# PGTN029_sequential_switch.net
KiCad netlist of a schematic drawn in EAGLE
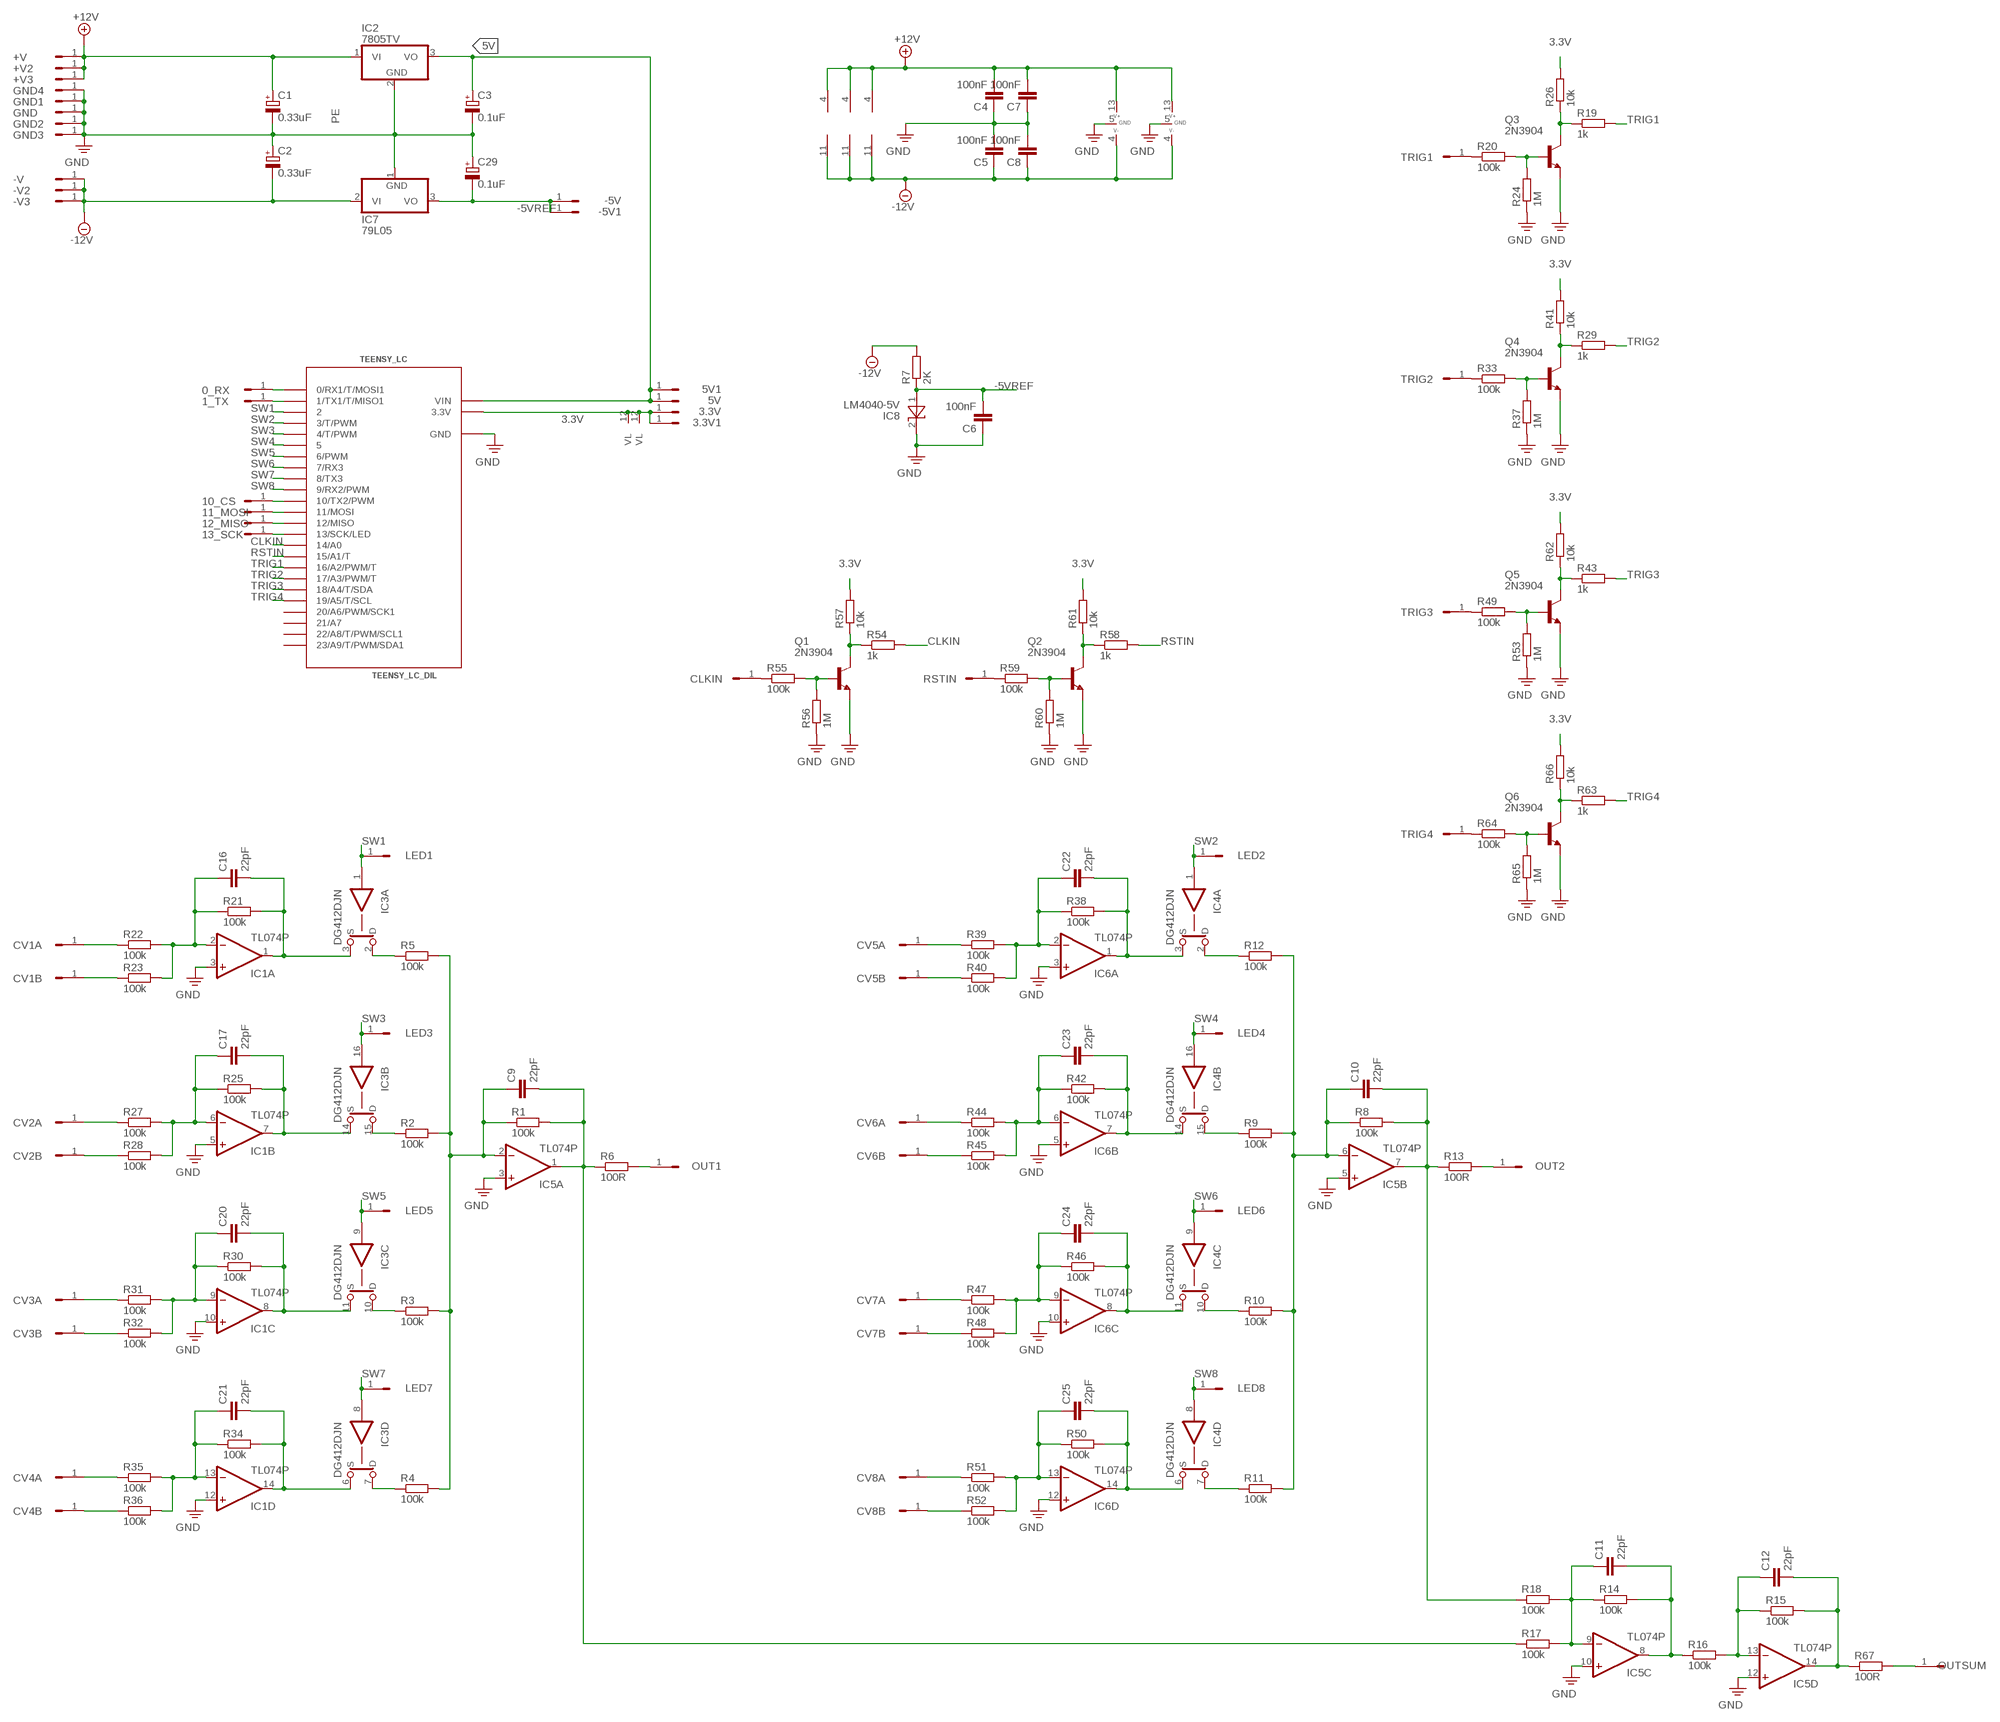
[diagram p0: schematic, sheet 1]

(export (version "E")
  (design (tool "Eeschema 10.0.6"))
  (components
    (comp (ref "+V")
      (value "HEADER/MALE/01")
      (footprint "eagle-import:HEADER_MALE_01")
      (fields (field (name "SPICEPREFIX") "X"))
      (libsource (lib "eagle-import") (part "HEADER/MALE/01"))
    )
    (comp (ref "+V2")
      (value "HEADER/MALE/01")
      (footprint "eagle-import:HEADER_MALE_01")
      (fields (field (name "SPICEPREFIX") "X"))
      (libsource (lib "eagle-import") (part "HEADER/MALE/01"))
    )
    (comp (ref "+V3")
      (value "HEADER/MALE/01")
      (footprint "eagle-import:HEADER_MALE_01")
      (fields (field (name "SPICEPREFIX") "X"))
      (libsource (lib "eagle-import") (part "HEADER/MALE/01"))
    )
    (comp (ref "-5V")
      (value "HEADER/MALE/01")
      (footprint "eagle-import:HEADER_MALE_01")
      (fields (field (name "SPICEPREFIX") "X"))
      (libsource (lib "eagle-import") (part "HEADER/MALE/01"))
    )
    (comp (ref "-5V1")
      (value "HEADER/MALE/01")
      (footprint "eagle-import:HEADER_MALE_01")
      (fields (field (name "SPICEPREFIX") "X"))
      (libsource (lib "eagle-import") (part "HEADER/MALE/01"))
    )
    (comp (ref "-V")
      (value "HEADER/MALE/01")
      (footprint "eagle-import:HEADER_MALE_01")
      (fields (field (name "SPICEPREFIX") "X"))
      (libsource (lib "eagle-import") (part "HEADER/MALE/01"))
    )
    (comp (ref "-V2")
      (value "HEADER/MALE/01")
      (footprint "eagle-import:HEADER_MALE_01")
      (fields (field (name "SPICEPREFIX") "X"))
      (libsource (lib "eagle-import") (part "HEADER/MALE/01"))
    )
    (comp (ref "-V3")
      (value "HEADER/MALE/01")
      (footprint "eagle-import:HEADER_MALE_01")
      (fields (field (name "SPICEPREFIX") "X"))
      (libsource (lib "eagle-import") (part "HEADER/MALE/01"))
    )
    (comp (ref "0_RX")
      (value "HEADER/MALE/01")
      (footprint "eagle-import:HEADER_MALE_01")
      (fields (field (name "SPICEPREFIX") "X"))
      (libsource (lib "eagle-import") (part "HEADER/MALE/01"))
    )
    (comp (ref "1_TX")
      (value "HEADER/MALE/01")
      (footprint "eagle-import:HEADER_MALE_01")
      (fields (field (name "SPICEPREFIX") "X"))
      (libsource (lib "eagle-import") (part "HEADER/MALE/01"))
    )
    (comp (ref "3.3V")
      (value "HEADER/MALE/01")
      (footprint "eagle-import:HEADER_MALE_01")
      (fields (field (name "SPICEPREFIX") "X"))
      (libsource (lib "eagle-import") (part "HEADER/MALE/01"))
    )
    (comp (ref "3.3V1")
      (value "HEADER/MALE/01")
      (footprint "eagle-import:HEADER_MALE_01")
      (fields (field (name "SPICEPREFIX") "X"))
      (libsource (lib "eagle-import") (part "HEADER/MALE/01"))
    )
    (comp (ref "5V")
      (value "HEADER/MALE/01")
      (footprint "eagle-import:HEADER_MALE_01")
      (fields (field (name "SPICEPREFIX") "X"))
      (libsource (lib "eagle-import") (part "HEADER/MALE/01"))
    )
    (comp (ref "5V1")
      (value "HEADER/MALE/01")
      (footprint "eagle-import:HEADER_MALE_01")
      (fields (field (name "SPICEPREFIX") "X"))
      (libsource (lib "eagle-import") (part "HEADER/MALE/01"))
    )
    (comp (ref "10_CS")
      (value "HEADER/MALE/01")
      (footprint "eagle-import:HEADER_MALE_01")
      (fields (field (name "SPICEPREFIX") "X"))
      (libsource (lib "eagle-import") (part "HEADER/MALE/01"))
    )
    (comp (ref "11_MOSI")
      (value "HEADER/MALE/01")
      (footprint "eagle-import:HEADER_MALE_01")
      (fields (field (name "SPICEPREFIX") "X"))
      (libsource (lib "eagle-import") (part "HEADER/MALE/01"))
    )
    (comp (ref "12_MISO")
      (value "HEADER/MALE/01")
      (footprint "eagle-import:HEADER_MALE_01")
      (fields (field (name "SPICEPREFIX") "X"))
      (libsource (lib "eagle-import") (part "HEADER/MALE/01"))
    )
    (comp (ref "13_SCK")
      (value "HEADER/MALE/01")
      (footprint "eagle-import:HEADER_MALE_01")
      (fields (field (name "SPICEPREFIX") "X"))
      (libsource (lib "eagle-import") (part "HEADER/MALE/01"))
    )
    (comp (ref "C1")
      (value "0.33uF")
      (footprint "eagle-import:E2,5-6")
      (fields (field (name "SPICEPREFIX") "C"))
      (libsource (lib "eagle-import") (part "CAPACITOR/POLARIZEDE2.5-6"))
    )
    (comp (ref "C2")
      (value "0.33uF")
      (footprint "eagle-import:E2,5-6")
      (fields (field (name "SPICEPREFIX") "C"))
      (libsource (lib "eagle-import") (part "CAPACITOR/POLARIZEDE2.5-6"))
    )
    (comp (ref "C3")
      (value "0.1uF")
      (footprint "eagle-import:E2,5-6")
      (fields (field (name "SPICEPREFIX") "C"))
      (libsource (lib "eagle-import") (part "CAPACITOR/POLARIZEDE2.5-6"))
    )
    (comp (ref "C4")
      (value "100nF")
      (footprint "eagle-import:CERAMICDISC_5")
      (libsource (lib "eagle-import") (part "CAPACITORCERAMICDISC/5"))
    )
    (comp (ref "C5")
      (value "100nF")
      (footprint "eagle-import:CERAMICDISC_5")
      (libsource (lib "eagle-import") (part "CAPACITORCERAMICDISC/5"))
    )
    (comp (ref "C6")
      (value "100nF")
      (footprint "eagle-import:CERAMICDISC_5")
      (libsource (lib "eagle-import") (part "CAPACITORCERAMICDISC/5"))
    )
    (comp (ref "C7")
      (value "100nF")
      (footprint "eagle-import:CERAMICDISC_5")
      (libsource (lib "eagle-import") (part "CAPACITORCERAMICDISC/5"))
    )
    (comp (ref "C8")
      (value "100nF")
      (footprint "eagle-import:CERAMICDISC_5")
      (libsource (lib "eagle-import") (part "CAPACITORCERAMICDISC/5"))
    )
    (comp (ref "C9")
      (value "22pF")
      (footprint "eagle-import:CERAMICDISC_5")
      (libsource (lib "eagle-import") (part "CAPACITORCERAMICDISC/5"))
    )
    (comp (ref "C10")
      (value "22pF")
      (footprint "eagle-import:CERAMICDISC_5")
      (libsource (lib "eagle-import") (part "CAPACITORCERAMICDISC/5"))
    )
    (comp (ref "C11")
      (value "22pF")
      (footprint "eagle-import:CERAMICDISC_5")
      (libsource (lib "eagle-import") (part "CAPACITORCERAMICDISC/5"))
    )
    (comp (ref "C12")
      (value "22pF")
      (footprint "eagle-import:CERAMICDISC_5")
      (libsource (lib "eagle-import") (part "CAPACITORCERAMICDISC/5"))
    )
    (comp (ref "C16")
      (value "22pF")
      (footprint "eagle-import:CERAMICDISC_5")
      (libsource (lib "eagle-import") (part "CAPACITORCERAMICDISC/5"))
    )
    (comp (ref "C17")
      (value "22pF")
      (footprint "eagle-import:CERAMICDISC_5")
      (libsource (lib "eagle-import") (part "CAPACITORCERAMICDISC/5"))
    )
    (comp (ref "C20")
      (value "22pF")
      (footprint "eagle-import:CERAMICDISC_5")
      (libsource (lib "eagle-import") (part "CAPACITORCERAMICDISC/5"))
    )
    (comp (ref "C21")
      (value "22pF")
      (footprint "eagle-import:CERAMICDISC_5")
      (libsource (lib "eagle-import") (part "CAPACITORCERAMICDISC/5"))
    )
    (comp (ref "C22")
      (value "22pF")
      (footprint "eagle-import:CERAMICDISC_5")
      (libsource (lib "eagle-import") (part "CAPACITORCERAMICDISC/5"))
    )
    (comp (ref "C23")
      (value "22pF")
      (footprint "eagle-import:CERAMICDISC_5")
      (libsource (lib "eagle-import") (part "CAPACITORCERAMICDISC/5"))
    )
    (comp (ref "C24")
      (value "22pF")
      (footprint "eagle-import:CERAMICDISC_5")
      (libsource (lib "eagle-import") (part "CAPACITORCERAMICDISC/5"))
    )
    (comp (ref "C25")
      (value "22pF")
      (footprint "eagle-import:CERAMICDISC_5")
      (libsource (lib "eagle-import") (part "CAPACITORCERAMICDISC/5"))
    )
    (comp (ref "C29")
      (value "0.1uF")
      (footprint "eagle-import:E2,5-6")
      (fields (field (name "SPICEPREFIX") "C"))
      (libsource (lib "eagle-import") (part "CAPACITOR/POLARIZEDE2.5-6"))
    )
    (comp (ref "CLKIN")
      (value "HEADER/MALE/01")
      (footprint "eagle-import:HEADER_MALE_01")
      (fields (field (name "SPICEPREFIX") "X"))
      (libsource (lib "eagle-import") (part "HEADER/MALE/01"))
    )
    (comp (ref "CV1A")
      (value "HEADER/MALE/01")
      (footprint "eagle-import:HEADER_MALE_01")
      (fields (field (name "SPICEPREFIX") "X"))
      (libsource (lib "eagle-import") (part "HEADER/MALE/01"))
    )
    (comp (ref "CV1B")
      (value "HEADER/MALE/01")
      (footprint "eagle-import:HEADER_MALE_01")
      (fields (field (name "SPICEPREFIX") "X"))
      (libsource (lib "eagle-import") (part "HEADER/MALE/01"))
    )
    (comp (ref "CV2A")
      (value "HEADER/MALE/01")
      (footprint "eagle-import:HEADER_MALE_01")
      (fields (field (name "SPICEPREFIX") "X"))
      (libsource (lib "eagle-import") (part "HEADER/MALE/01"))
    )
    (comp (ref "CV2B")
      (value "HEADER/MALE/01")
      (footprint "eagle-import:HEADER_MALE_01")
      (fields (field (name "SPICEPREFIX") "X"))
      (libsource (lib "eagle-import") (part "HEADER/MALE/01"))
    )
    (comp (ref "CV3A")
      (value "HEADER/MALE/01")
      (footprint "eagle-import:HEADER_MALE_01")
      (fields (field (name "SPICEPREFIX") "X"))
      (libsource (lib "eagle-import") (part "HEADER/MALE/01"))
    )
    (comp (ref "CV3B")
      (value "HEADER/MALE/01")
      (footprint "eagle-import:HEADER_MALE_01")
      (fields (field (name "SPICEPREFIX") "X"))
      (libsource (lib "eagle-import") (part "HEADER/MALE/01"))
    )
    (comp (ref "CV4A")
      (value "HEADER/MALE/01")
      (footprint "eagle-import:HEADER_MALE_01")
      (fields (field (name "SPICEPREFIX") "X"))
      (libsource (lib "eagle-import") (part "HEADER/MALE/01"))
    )
    (comp (ref "CV4B")
      (value "HEADER/MALE/01")
      (footprint "eagle-import:HEADER_MALE_01")
      (fields (field (name "SPICEPREFIX") "X"))
      (libsource (lib "eagle-import") (part "HEADER/MALE/01"))
    )
    (comp (ref "CV5A")
      (value "HEADER/MALE/01")
      (footprint "eagle-import:HEADER_MALE_01")
      (fields (field (name "SPICEPREFIX") "X"))
      (libsource (lib "eagle-import") (part "HEADER/MALE/01"))
    )
    (comp (ref "CV5B")
      (value "HEADER/MALE/01")
      (footprint "eagle-import:HEADER_MALE_01")
      (fields (field (name "SPICEPREFIX") "X"))
      (libsource (lib "eagle-import") (part "HEADER/MALE/01"))
    )
    (comp (ref "CV6A")
      (value "HEADER/MALE/01")
      (footprint "eagle-import:HEADER_MALE_01")
      (fields (field (name "SPICEPREFIX") "X"))
      (libsource (lib "eagle-import") (part "HEADER/MALE/01"))
    )
    (comp (ref "CV6B")
      (value "HEADER/MALE/01")
      (footprint "eagle-import:HEADER_MALE_01")
      (fields (field (name "SPICEPREFIX") "X"))
      (libsource (lib "eagle-import") (part "HEADER/MALE/01"))
    )
    (comp (ref "CV7A")
      (value "HEADER/MALE/01")
      (footprint "eagle-import:HEADER_MALE_01")
      (fields (field (name "SPICEPREFIX") "X"))
      (libsource (lib "eagle-import") (part "HEADER/MALE/01"))
    )
    (comp (ref "CV7B")
      (value "HEADER/MALE/01")
      (footprint "eagle-import:HEADER_MALE_01")
      (fields (field (name "SPICEPREFIX") "X"))
      (libsource (lib "eagle-import") (part "HEADER/MALE/01"))
    )
    (comp (ref "CV8A")
      (value "HEADER/MALE/01")
      (footprint "eagle-import:HEADER_MALE_01")
      (fields (field (name "SPICEPREFIX") "X"))
      (libsource (lib "eagle-import") (part "HEADER/MALE/01"))
    )
    (comp (ref "CV8B")
      (value "HEADER/MALE/01")
      (footprint "eagle-import:HEADER_MALE_01")
      (fields (field (name "SPICEPREFIX") "X"))
      (libsource (lib "eagle-import") (part "HEADER/MALE/01"))
    )
    (comp (ref "GND")
      (value "HEADER/MALE/01")
      (footprint "eagle-import:HEADER_MALE_01")
      (fields (field (name "SPICEPREFIX") "X"))
      (libsource (lib "eagle-import") (part "HEADER/MALE/01"))
    )
    (comp (ref "GND1")
      (value "HEADER/MALE/01")
      (footprint "eagle-import:HEADER_MALE_01")
      (fields (field (name "SPICEPREFIX") "X"))
      (libsource (lib "eagle-import") (part "HEADER/MALE/01"))
    )
    (comp (ref "GND2")
      (value "HEADER/MALE/01")
      (footprint "eagle-import:HEADER_MALE_01")
      (fields (field (name "SPICEPREFIX") "X"))
      (libsource (lib "eagle-import") (part "HEADER/MALE/01"))
    )
    (comp (ref "GND3")
      (value "HEADER/MALE/01")
      (footprint "eagle-import:HEADER_MALE_01")
      (fields (field (name "SPICEPREFIX") "X"))
      (libsource (lib "eagle-import") (part "HEADER/MALE/01"))
    )
    (comp (ref "GND4")
      (value "HEADER/MALE/01")
      (footprint "eagle-import:HEADER_MALE_01")
      (fields (field (name "SPICEPREFIX") "X"))
      (libsource (lib "eagle-import") (part "HEADER/MALE/01"))
    )
    (comp (ref "IC1")
      (value "TL074P")
      (footprint "eagle-import:DIL14")
      (libsource (lib "eagle-import") (part "TL074P"))
    )
    (comp (ref "IC2")
      (value "7805TV")
      (footprint "eagle-import:TO220V")
      (libsource (lib "eagle-import") (part "78TV05"))
    )
    (comp (ref "IC3")
      (value "DG412DJN")
      (footprint "eagle-import:DIL16")
      (libsource (lib "eagle-import") (part "DG412DJN"))
    )
    (comp (ref "IC4")
      (value "DG412DJN")
      (footprint "eagle-import:DIL16")
      (libsource (lib "eagle-import") (part "DG412DJN"))
    )
    (comp (ref "IC5")
      (value "TL074P")
      (footprint "eagle-import:DIL14")
      (libsource (lib "eagle-import") (part "TL074P"))
    )
    (comp (ref "IC6")
      (value "TL074P")
      (footprint "eagle-import:DIL14")
      (libsource (lib "eagle-import") (part "TL074P"))
    )
    (comp (ref "IC7")
      (value "79L05")
      (footprint "eagle-import:TO92")
      (libsource (lib "eagle-import") (part "79ZL05"))
    )
    (comp (ref "IC8")
      (value "LM4040-5V")
      (footprint "eagle-import:TO92")
      (libsource (lib "eagle-import") (part "LM4040"))
    )
    (comp (ref "LED1")
      (value "HEADER/MALE/01")
      (footprint "eagle-import:HEADER_MALE_01")
      (fields (field (name "SPICEPREFIX") "X"))
      (libsource (lib "eagle-import") (part "HEADER/MALE/01"))
    )
    (comp (ref "LED2")
      (value "HEADER/MALE/01")
      (footprint "eagle-import:HEADER_MALE_01")
      (fields (field (name "SPICEPREFIX") "X"))
      (libsource (lib "eagle-import") (part "HEADER/MALE/01"))
    )
    (comp (ref "LED3")
      (value "HEADER/MALE/01")
      (footprint "eagle-import:HEADER_MALE_01")
      (fields (field (name "SPICEPREFIX") "X"))
      (libsource (lib "eagle-import") (part "HEADER/MALE/01"))
    )
    (comp (ref "LED4")
      (value "HEADER/MALE/01")
      (footprint "eagle-import:HEADER_MALE_01")
      (fields (field (name "SPICEPREFIX") "X"))
      (libsource (lib "eagle-import") (part "HEADER/MALE/01"))
    )
    (comp (ref "LED5")
      (value "HEADER/MALE/01")
      (footprint "eagle-import:HEADER_MALE_01")
      (fields (field (name "SPICEPREFIX") "X"))
      (libsource (lib "eagle-import") (part "HEADER/MALE/01"))
    )
    (comp (ref "LED6")
      (value "HEADER/MALE/01")
      (footprint "eagle-import:HEADER_MALE_01")
      (fields (field (name "SPICEPREFIX") "X"))
      (libsource (lib "eagle-import") (part "HEADER/MALE/01"))
    )
    (comp (ref "LED7")
      (value "HEADER/MALE/01")
      (footprint "eagle-import:HEADER_MALE_01")
      (fields (field (name "SPICEPREFIX") "X"))
      (libsource (lib "eagle-import") (part "HEADER/MALE/01"))
    )
    (comp (ref "LED8")
      (value "HEADER/MALE/01")
      (footprint "eagle-import:HEADER_MALE_01")
      (fields (field (name "SPICEPREFIX") "X"))
      (libsource (lib "eagle-import") (part "HEADER/MALE/01"))
    )
    (comp (ref "OUT1")
      (value "HEADER/MALE/01")
      (footprint "eagle-import:HEADER_MALE_01")
      (fields (field (name "SPICEPREFIX") "X"))
      (libsource (lib "eagle-import") (part "HEADER/MALE/01"))
    )
    (comp (ref "OUT2")
      (value "HEADER/MALE/01")
      (footprint "eagle-import:HEADER_MALE_01")
      (fields (field (name "SPICEPREFIX") "X"))
      (libsource (lib "eagle-import") (part "HEADER/MALE/01"))
    )
    (comp (ref "OUTSUM")
      (value "HEADER/MALE/01")
      (footprint "eagle-import:HEADER_MALE_01")
      (fields (field (name "SPICEPREFIX") "X"))
      (libsource (lib "eagle-import") (part "HEADER/MALE/01"))
    )
    (comp (ref "Q1")
      (value "2N3904")
      (footprint "eagle-import:TO92")
      (libsource (lib "eagle-import") (part "2N3904"))
    )
    (comp (ref "Q2")
      (value "2N3904")
      (footprint "eagle-import:TO92")
      (libsource (lib "eagle-import") (part "2N3904"))
    )
    (comp (ref "Q3")
      (value "2N3904")
      (footprint "eagle-import:TO92")
      (libsource (lib "eagle-import") (part "2N3904"))
    )
    (comp (ref "Q4")
      (value "2N3904")
      (footprint "eagle-import:TO92")
      (libsource (lib "eagle-import") (part "2N3904"))
    )
    (comp (ref "Q5")
      (value "2N3904")
      (footprint "eagle-import:TO92")
      (libsource (lib "eagle-import") (part "2N3904"))
    )
    (comp (ref "Q6")
      (value "2N3904")
      (footprint "eagle-import:TO92")
      (libsource (lib "eagle-import") (part "2N3904"))
    )
    (comp (ref "R1")
      (value "100k")
      (footprint "eagle-import:RESISTOR_7.5")
      (libsource (lib "eagle-import") (part "RESISTORRESISTOR/UPRIGHT/7.5"))
    )
    (comp (ref "R2")
      (value "100k")
      (footprint "eagle-import:RESISTOR_7.5")
      (libsource (lib "eagle-import") (part "RESISTORRESISTOR/UPRIGHT/7.5"))
    )
    (comp (ref "R3")
      (value "100k")
      (footprint "eagle-import:RESISTOR_7.5")
      (libsource (lib "eagle-import") (part "RESISTORRESISTOR/UPRIGHT/7.5"))
    )
    (comp (ref "R4")
      (value "100k")
      (footprint "eagle-import:RESISTOR_7.5")
      (libsource (lib "eagle-import") (part "RESISTORRESISTOR/UPRIGHT/7.5"))
    )
    (comp (ref "R5")
      (value "100k")
      (footprint "eagle-import:RESISTOR_7.5")
      (libsource (lib "eagle-import") (part "RESISTORRESISTOR/UPRIGHT/7.5"))
    )
    (comp (ref "R6")
      (value "100R")
      (footprint "eagle-import:RESISTOR_7.5")
      (libsource (lib "eagle-import") (part "RESISTORRESISTOR/UPRIGHT/7.5"))
    )
    (comp (ref "R7")
      (value "2K")
      (footprint "eagle-import:RESISTOR_7.5")
      (libsource (lib "eagle-import") (part "RESISTORRESISTOR/UPRIGHT/7.5"))
    )
    (comp (ref "R8")
      (value "100k")
      (footprint "eagle-import:RESISTOR_7.5")
      (libsource (lib "eagle-import") (part "RESISTORRESISTOR/UPRIGHT/7.5"))
    )
    (comp (ref "R9")
      (value "100k")
      (footprint "eagle-import:RESISTOR_7.5")
      (libsource (lib "eagle-import") (part "RESISTORRESISTOR/UPRIGHT/7.5"))
    )
    (comp (ref "R10")
      (value "100k")
      (footprint "eagle-import:RESISTOR_7.5")
      (libsource (lib "eagle-import") (part "RESISTORRESISTOR/UPRIGHT/7.5"))
    )
    (comp (ref "R11")
      (value "100k")
      (footprint "eagle-import:RESISTOR_7.5")
      (libsource (lib "eagle-import") (part "RESISTORRESISTOR/UPRIGHT/7.5"))
    )
    (comp (ref "R12")
      (value "100k")
      (footprint "eagle-import:RESISTOR_7.5")
      (libsource (lib "eagle-import") (part "RESISTORRESISTOR/UPRIGHT/7.5"))
    )
    (comp (ref "R13")
      (value "100R")
      (footprint "eagle-import:RESISTOR_7.5")
      (libsource (lib "eagle-import") (part "RESISTORRESISTOR/UPRIGHT/7.5"))
    )
    (comp (ref "R14")
      (value "100k")
      (footprint "eagle-import:RESISTOR_7.5")
      (libsource (lib "eagle-import") (part "RESISTORRESISTOR/UPRIGHT/7.5"))
    )
    (comp (ref "R15")
      (value "100k")
      (footprint "eagle-import:RESISTOR_7.5")
      (libsource (lib "eagle-import") (part "RESISTORRESISTOR/UPRIGHT/7.5"))
    )
    (comp (ref "R16")
      (value "100k")
      (footprint "eagle-import:RESISTOR_7.5")
      (libsource (lib "eagle-import") (part "RESISTORRESISTOR/UPRIGHT/7.5"))
    )
    (comp (ref "R17")
      (value "100k")
      (footprint "eagle-import:RESISTOR_7.5")
      (libsource (lib "eagle-import") (part "RESISTORRESISTOR/UPRIGHT/7.5"))
    )
    (comp (ref "R18")
      (value "100k")
      (footprint "eagle-import:RESISTOR_7.5")
      (libsource (lib "eagle-import") (part "RESISTORRESISTOR/UPRIGHT/7.5"))
    )
    (comp (ref "R19")
      (value "1k")
      (footprint "eagle-import:RESISTOR_7.5")
      (libsource (lib "eagle-import") (part "RESISTORRESISTOR/UPRIGHT/7.5"))
    )
    (comp (ref "R20")
      (value "100k")
      (footprint "eagle-import:RESISTOR_7.5")
      (libsource (lib "eagle-import") (part "RESISTORRESISTOR/UPRIGHT/7.5"))
    )
    (comp (ref "R21")
      (value "100k")
      (footprint "eagle-import:RESISTOR_7.5")
      (libsource (lib "eagle-import") (part "RESISTORRESISTOR/UPRIGHT/7.5"))
    )
    (comp (ref "R22")
      (value "100k")
      (footprint "eagle-import:RESISTOR_7.5")
      (libsource (lib "eagle-import") (part "RESISTORRESISTOR/UPRIGHT/7.5"))
    )
    (comp (ref "R23")
      (value "100k")
      (footprint "eagle-import:RESISTOR_7.5")
      (libsource (lib "eagle-import") (part "RESISTORRESISTOR/UPRIGHT/7.5"))
    )
    (comp (ref "R24")
      (value "1M")
      (footprint "eagle-import:RESISTOR_7.5")
      (libsource (lib "eagle-import") (part "RESISTORRESISTOR/UPRIGHT/7.5"))
    )
    (comp (ref "R25")
      (value "100k")
      (footprint "eagle-import:RESISTOR_7.5")
      (libsource (lib "eagle-import") (part "RESISTORRESISTOR/UPRIGHT/7.5"))
    )
    (comp (ref "R26")
      (value "10k")
      (footprint "eagle-import:RESISTOR_7.5")
      (libsource (lib "eagle-import") (part "RESISTORRESISTOR/UPRIGHT/7.5"))
    )
    (comp (ref "R27")
      (value "100k")
      (footprint "eagle-import:RESISTOR_7.5")
      (libsource (lib "eagle-import") (part "RESISTORRESISTOR/UPRIGHT/7.5"))
    )
    (comp (ref "R28")
      (value "100k")
      (footprint "eagle-import:RESISTOR_7.5")
      (libsource (lib "eagle-import") (part "RESISTORRESISTOR/UPRIGHT/7.5"))
    )
    (comp (ref "R29")
      (value "1k")
      (footprint "eagle-import:RESISTOR_7.5")
      (libsource (lib "eagle-import") (part "RESISTORRESISTOR/UPRIGHT/7.5"))
    )
    (comp (ref "R30")
      (value "100k")
      (footprint "eagle-import:RESISTOR_7.5")
      (libsource (lib "eagle-import") (part "RESISTORRESISTOR/UPRIGHT/7.5"))
    )
    (comp (ref "R31")
      (value "100k")
      (footprint "eagle-import:RESISTOR_7.5")
      (libsource (lib "eagle-import") (part "RESISTORRESISTOR/UPRIGHT/7.5"))
    )
    (comp (ref "R32")
      (value "100k")
      (footprint "eagle-import:RESISTOR_7.5")
      (libsource (lib "eagle-import") (part "RESISTORRESISTOR/UPRIGHT/7.5"))
    )
    (comp (ref "R33")
      (value "100k")
      (footprint "eagle-import:RESISTOR_7.5")
      (libsource (lib "eagle-import") (part "RESISTORRESISTOR/UPRIGHT/7.5"))
    )
    (comp (ref "R34")
      (value "100k")
      (footprint "eagle-import:RESISTOR_7.5")
      (libsource (lib "eagle-import") (part "RESISTORRESISTOR/UPRIGHT/7.5"))
    )
    (comp (ref "R35")
      (value "100k")
      (footprint "eagle-import:RESISTOR_7.5")
      (libsource (lib "eagle-import") (part "RESISTORRESISTOR/UPRIGHT/7.5"))
    )
    (comp (ref "R36")
      (value "100k")
      (footprint "eagle-import:RESISTOR_7.5")
      (libsource (lib "eagle-import") (part "RESISTORRESISTOR/UPRIGHT/7.5"))
    )
    (comp (ref "R37")
      (value "1M")
      (footprint "eagle-import:RESISTOR_7.5")
      (libsource (lib "eagle-import") (part "RESISTORRESISTOR/UPRIGHT/7.5"))
    )
    (comp (ref "R38")
      (value "100k")
      (footprint "eagle-import:RESISTOR_7.5")
      (libsource (lib "eagle-import") (part "RESISTORRESISTOR/UPRIGHT/7.5"))
    )
    (comp (ref "R39")
      (value "100k")
      (footprint "eagle-import:RESISTOR_7.5")
      (libsource (lib "eagle-import") (part "RESISTORRESISTOR/UPRIGHT/7.5"))
    )
    (comp (ref "R40")
      (value "100k")
      (footprint "eagle-import:RESISTOR_7.5")
      (libsource (lib "eagle-import") (part "RESISTORRESISTOR/UPRIGHT/7.5"))
    )
    (comp (ref "R41")
      (value "10k")
      (footprint "eagle-import:RESISTOR_7.5")
      (libsource (lib "eagle-import") (part "RESISTORRESISTOR/UPRIGHT/7.5"))
    )
    (comp (ref "R42")
      (value "100k")
      (footprint "eagle-import:RESISTOR_7.5")
      (libsource (lib "eagle-import") (part "RESISTORRESISTOR/UPRIGHT/7.5"))
    )
    (comp (ref "R43")
      (value "1k")
      (footprint "eagle-import:RESISTOR_7.5")
      (libsource (lib "eagle-import") (part "RESISTORRESISTOR/UPRIGHT/7.5"))
    )
    (comp (ref "R44")
      (value "100k")
      (footprint "eagle-import:RESISTOR_7.5")
      (libsource (lib "eagle-import") (part "RESISTORRESISTOR/UPRIGHT/7.5"))
    )
    (comp (ref "R45")
      (value "100k")
      (footprint "eagle-import:RESISTOR_7.5")
      (libsource (lib "eagle-import") (part "RESISTORRESISTOR/UPRIGHT/7.5"))
    )
    (comp (ref "R46")
      (value "100k")
      (footprint "eagle-import:RESISTOR_7.5")
      (libsource (lib "eagle-import") (part "RESISTORRESISTOR/UPRIGHT/7.5"))
    )
    (comp (ref "R47")
      (value "100k")
      (footprint "eagle-import:RESISTOR_7.5")
      (libsource (lib "eagle-import") (part "RESISTORRESISTOR/UPRIGHT/7.5"))
    )
    (comp (ref "R48")
      (value "100k")
      (footprint "eagle-import:RESISTOR_7.5")
      (libsource (lib "eagle-import") (part "RESISTORRESISTOR/UPRIGHT/7.5"))
    )
    (comp (ref "R49")
      (value "100k")
      (footprint "eagle-import:RESISTOR_7.5")
      (libsource (lib "eagle-import") (part "RESISTORRESISTOR/UPRIGHT/7.5"))
    )
    (comp (ref "R50")
      (value "100k")
      (footprint "eagle-import:RESISTOR_7.5")
      (libsource (lib "eagle-import") (part "RESISTORRESISTOR/UPRIGHT/7.5"))
    )
    (comp (ref "R51")
      (value "100k")
      (footprint "eagle-import:RESISTOR_7.5")
      (libsource (lib "eagle-import") (part "RESISTORRESISTOR/UPRIGHT/7.5"))
    )
    (comp (ref "R52")
      (value "100k")
      (footprint "eagle-import:RESISTOR_7.5")
      (libsource (lib "eagle-import") (part "RESISTORRESISTOR/UPRIGHT/7.5"))
    )
    (comp (ref "R53")
      (value "1M")
      (footprint "eagle-import:RESISTOR_7.5")
      (libsource (lib "eagle-import") (part "RESISTORRESISTOR/UPRIGHT/7.5"))
    )
    (comp (ref "R54")
      (value "1k")
      (footprint "eagle-import:RESISTOR_7.5")
      (libsource (lib "eagle-import") (part "RESISTORRESISTOR/UPRIGHT/7.5"))
    )
    (comp (ref "R55")
      (value "100k")
      (footprint "eagle-import:RESISTOR_7.5")
      (libsource (lib "eagle-import") (part "RESISTORRESISTOR/UPRIGHT/7.5"))
    )
    (comp (ref "R56")
      (value "1M")
      (footprint "eagle-import:RESISTOR_7.5")
      (libsource (lib "eagle-import") (part "RESISTORRESISTOR/UPRIGHT/7.5"))
    )
    (comp (ref "R57")
      (value "10k")
      (footprint "eagle-import:RESISTOR_7.5")
      (libsource (lib "eagle-import") (part "RESISTORRESISTOR/UPRIGHT/7.5"))
    )
    (comp (ref "R58")
      (value "1k")
      (footprint "eagle-import:RESISTOR_7.5")
      (libsource (lib "eagle-import") (part "RESISTORRESISTOR/UPRIGHT/7.5"))
    )
    (comp (ref "R59")
      (value "100k")
      (footprint "eagle-import:RESISTOR_7.5")
      (libsource (lib "eagle-import") (part "RESISTORRESISTOR/UPRIGHT/7.5"))
    )
    (comp (ref "R60")
      (value "1M")
      (footprint "eagle-import:RESISTOR_7.5")
      (libsource (lib "eagle-import") (part "RESISTORRESISTOR/UPRIGHT/7.5"))
    )
    (comp (ref "R61")
      (value "10k")
      (footprint "eagle-import:RESISTOR_7.5")
      (libsource (lib "eagle-import") (part "RESISTORRESISTOR/UPRIGHT/7.5"))
    )
    (comp (ref "R62")
      (value "10k")
      (footprint "eagle-import:RESISTOR_7.5")
      (libsource (lib "eagle-import") (part "RESISTORRESISTOR/UPRIGHT/7.5"))
    )
    (comp (ref "R63")
      (value "1k")
      (footprint "eagle-import:RESISTOR_7.5")
      (libsource (lib "eagle-import") (part "RESISTORRESISTOR/UPRIGHT/7.5"))
    )
    (comp (ref "R64")
      (value "100k")
      (footprint "eagle-import:RESISTOR_7.5")
      (libsource (lib "eagle-import") (part "RESISTORRESISTOR/UPRIGHT/7.5"))
    )
    (comp (ref "R65")
      (value "1M")
      (footprint "eagle-import:RESISTOR_7.5")
      (libsource (lib "eagle-import") (part "RESISTORRESISTOR/UPRIGHT/7.5"))
    )
    (comp (ref "R66")
      (value "10k")
      (footprint "eagle-import:RESISTOR_7.5")
      (libsource (lib "eagle-import") (part "RESISTORRESISTOR/UPRIGHT/7.5"))
    )
    (comp (ref "R67")
      (value "100R")
      (footprint "eagle-import:RESISTOR_7.5")
      (libsource (lib "eagle-import") (part "RESISTORRESISTOR/UPRIGHT/7.5"))
    )
    (comp (ref "RSTIN")
      (value "HEADER/MALE/01")
      (footprint "eagle-import:HEADER_MALE_01")
      (fields (field (name "SPICEPREFIX") "X"))
      (libsource (lib "eagle-import") (part "HEADER/MALE/01"))
    )
    (comp (ref "TEENSY_LC")
      (value "TEENSY_LC_DIL")
      (footprint "eagle-import:TEENSY_3.0-3.2&LC_DIL")
      (libsource (lib "eagle-import") (part "TEENSY_LC_DIL"))
    )
    (comp (ref "TRIG1")
      (value "HEADER/MALE/01")
      (footprint "eagle-import:HEADER_MALE_01")
      (fields (field (name "SPICEPREFIX") "X"))
      (libsource (lib "eagle-import") (part "HEADER/MALE/01"))
    )
    (comp (ref "TRIG2")
      (value "HEADER/MALE/01")
      (footprint "eagle-import:HEADER_MALE_01")
      (fields (field (name "SPICEPREFIX") "X"))
      (libsource (lib "eagle-import") (part "HEADER/MALE/01"))
    )
    (comp (ref "TRIG3")
      (value "HEADER/MALE/01")
      (footprint "eagle-import:HEADER_MALE_01")
      (fields (field (name "SPICEPREFIX") "X"))
      (libsource (lib "eagle-import") (part "HEADER/MALE/01"))
    )
    (comp (ref "TRIG4")
      (value "HEADER/MALE/01")
      (footprint "eagle-import:HEADER_MALE_01")
      (fields (field (name "SPICEPREFIX") "X"))
      (libsource (lib "eagle-import") (part "HEADER/MALE/01"))
    )
  )
  (nets
    (net (code "1") (name "+12V") (class "Default")
      (node (ref "+V") (pin "1") (pinfunction "3_1") (pintype "passive"))
      (node (ref "+V2") (pin "1") (pinfunction "3_1") (pintype "passive"))
      (node (ref "+V3") (pin "1") (pinfunction "3_1") (pintype "passive"))
      (node (ref "C1") (pin "+") (pinfunction "+_+") (pintype "passive"))
      (node (ref "C4") (pin "2") (pinfunction "2_2") (pintype "passive"))
      (node (ref "C7") (pin "2") (pinfunction "2_2") (pintype "passive"))
      (node (ref "IC1") (pin "4") (pinfunction "V+_4") (pintype "power_in"))
      (node (ref "IC2") (pin "1") (pinfunction "VI_1") (pintype "input"))
      (node (ref "IC3") (pin "13") (pinfunction "V+_13") (pintype "power_in"))
      (node (ref "IC4") (pin "13") (pinfunction "V+_13") (pintype "power_in"))
      (node (ref "IC5") (pin "4") (pinfunction "V+_4") (pintype "power_in"))
      (node (ref "IC6") (pin "4") (pinfunction "V+_4") (pintype "power_in"))
    )
    (net (code "2") (name "-12V") (class "Default")
      (node (ref "-V") (pin "1") (pinfunction "3_1") (pintype "passive"))
      (node (ref "-V2") (pin "1") (pinfunction "3_1") (pintype "passive"))
      (node (ref "-V3") (pin "1") (pinfunction "3_1") (pintype "passive"))
      (node (ref "C2") (pin "-") (pinfunction "-_-") (pintype "passive"))
      (node (ref "C5") (pin "1") (pinfunction "1_1") (pintype "passive"))
      (node (ref "C8") (pin "1") (pinfunction "1_1") (pintype "passive"))
      (node (ref "IC1") (pin "11") (pinfunction "V-_11") (pintype "power_in"))
      (node (ref "IC3") (pin "4") (pinfunction "V-_4") (pintype "power_in"))
      (node (ref "IC4") (pin "4") (pinfunction "V-_4") (pintype "power_in"))
      (node (ref "IC5") (pin "11") (pinfunction "V-_11") (pintype "power_in"))
      (node (ref "IC6") (pin "11") (pinfunction "V-_11") (pintype "power_in"))
      (node (ref "IC7") (pin "2") (pinfunction "VI_2") (pintype "input"))
      (node (ref "R7") (pin "2") (pinfunction "2_2") (pintype "passive"))
    )
    (net (code "3") (name "/-5VREF") (class "Default")
      (node (ref "-5V") (pin "1") (pinfunction "3_1") (pintype "passive"))
      (node (ref "-5V1") (pin "1") (pinfunction "3_1") (pintype "passive"))
      (node (ref "C29") (pin "-") (pinfunction "-_-") (pintype "passive"))
      (node (ref "C6") (pin "2") (pinfunction "2_2") (pintype "passive"))
      (node (ref "IC7") (pin "3") (pinfunction "VO_3") (pintype "passive"))
      (node (ref "IC8") (pin "1") (pinfunction "A_1") (pintype "output"))
      (node (ref "R7") (pin "1") (pinfunction "1_1") (pintype "passive"))
    )
    (net (code "4") (name "/3.3V") (class "Default")
      (node (ref "3.3V") (pin "1") (pinfunction "3_1") (pintype "passive"))
      (node (ref "3.3V1") (pin "1") (pinfunction "3_1") (pintype "passive"))
      (node (ref "IC3") (pin "12") (pinfunction "VL_12") (pintype "input"))
      (node (ref "IC4") (pin "12") (pinfunction "VL_12") (pintype "input"))
      (node (ref "R26") (pin "2") (pinfunction "2_2") (pintype "passive"))
      (node (ref "R41") (pin "2") (pinfunction "2_2") (pintype "passive"))
      (node (ref "R57") (pin "2") (pinfunction "2_2") (pintype "passive"))
      (node (ref "R61") (pin "2") (pinfunction "2_2") (pintype "passive"))
      (node (ref "R62") (pin "2") (pinfunction "2_2") (pintype "passive"))
      (node (ref "R66") (pin "2") (pinfunction "2_2") (pintype "passive"))
      (node (ref "TEENSY_LC") (pin "3.3V") (pinfunction "3.3V_3.3V") (pintype "power_in"))
    )
    (net (code "5") (name "/CLKIN") (class "Default")
      (node (ref "R54") (pin "2") (pinfunction "2_2") (pintype "passive"))
      (node (ref "TEENSY_LC") (pin "14/A0") (pinfunction "14/A0_14/A0") (pintype "bidirectional"))
    )
    (net (code "6") (name "/RSTIN") (class "Default")
      (node (ref "R58") (pin "2") (pinfunction "2_2") (pintype "passive"))
      (node (ref "TEENSY_LC") (pin "15/A1") (pinfunction "15/A1/T_15/A1") (pintype "bidirectional"))
    )
    (net (code "7") (name "/SW1") (class "Default")
      (node (ref "IC3") (pin "1") (pinfunction "IN_1") (pintype "input"))
      (node (ref "LED1") (pin "1") (pinfunction "3_1") (pintype "passive"))
      (node (ref "TEENSY_LC") (pin "2") (pinfunction "2_2") (pintype "bidirectional"))
    )
    (net (code "8") (name "/SW2") (class "Default")
      (node (ref "IC4") (pin "1") (pinfunction "IN_1") (pintype "input"))
      (node (ref "LED2") (pin "1") (pinfunction "3_1") (pintype "passive"))
      (node (ref "TEENSY_LC") (pin "3") (pinfunction "3/T/PWM_3") (pintype "bidirectional"))
    )
    (net (code "9") (name "/SW3") (class "Default")
      (node (ref "IC3") (pin "16") (pinfunction "IN_16") (pintype "input"))
      (node (ref "LED3") (pin "1") (pinfunction "3_1") (pintype "passive"))
      (node (ref "TEENSY_LC") (pin "4") (pinfunction "4/T/PWM_4") (pintype "bidirectional"))
    )
    (net (code "10") (name "/SW4") (class "Default")
      (node (ref "IC4") (pin "16") (pinfunction "IN_16") (pintype "input"))
      (node (ref "LED4") (pin "1") (pinfunction "3_1") (pintype "passive"))
      (node (ref "TEENSY_LC") (pin "5") (pinfunction "5_5") (pintype "bidirectional"))
    )
    (net (code "11") (name "/SW5") (class "Default")
      (node (ref "IC3") (pin "9") (pinfunction "IN_9") (pintype "input"))
      (node (ref "LED5") (pin "1") (pinfunction "3_1") (pintype "passive"))
      (node (ref "TEENSY_LC") (pin "6") (pinfunction "6/PWM_6") (pintype "bidirectional"))
    )
    (net (code "12") (name "/SW6") (class "Default")
      (node (ref "IC4") (pin "9") (pinfunction "IN_9") (pintype "input"))
      (node (ref "LED6") (pin "1") (pinfunction "3_1") (pintype "passive"))
      (node (ref "TEENSY_LC") (pin "7") (pinfunction "7/RX3_7") (pintype "bidirectional"))
    )
    (net (code "13") (name "/SW7") (class "Default")
      (node (ref "IC3") (pin "8") (pinfunction "IN_8") (pintype "input"))
      (node (ref "LED7") (pin "1") (pinfunction "3_1") (pintype "passive"))
      (node (ref "TEENSY_LC") (pin "8") (pinfunction "8/TX3_8") (pintype "bidirectional"))
    )
    (net (code "14") (name "/SW8") (class "Default")
      (node (ref "IC4") (pin "8") (pinfunction "IN_8") (pintype "input"))
      (node (ref "LED8") (pin "1") (pinfunction "3_1") (pintype "passive"))
      (node (ref "TEENSY_LC") (pin "9") (pinfunction "9/RX2/PWM_9") (pintype "bidirectional"))
    )
    (net (code "15") (name "/TRIG1") (class "Default")
      (node (ref "R19") (pin "2") (pinfunction "2_2") (pintype "passive"))
      (node (ref "TEENSY_LC") (pin "16/A2") (pinfunction "16/A2/PWM/T_16/A2") (pintype "bidirectional"))
    )
    (net (code "16") (name "/TRIG2") (class "Default")
      (node (ref "R29") (pin "2") (pinfunction "2_2") (pintype "passive"))
      (node (ref "TEENSY_LC") (pin "17/A3") (pinfunction "17/A3/PWM/T_17/A3") (pintype "bidirectional"))
    )
    (net (code "17") (name "/TRIG3") (class "Default")
      (node (ref "R43") (pin "2") (pinfunction "2_2") (pintype "passive"))
      (node (ref "TEENSY_LC") (pin "18/A4") (pinfunction "18/A4/T/SDA_18/A4") (pintype "bidirectional"))
    )
    (net (code "18") (name "/TRIG4") (class "Default")
      (node (ref "R63") (pin "2") (pinfunction "2_2") (pintype "passive"))
      (node (ref "TEENSY_LC") (pin "19/A5") (pinfunction "19/A5/T/SCL_19/A5") (pintype "bidirectional"))
    )
    (net (code "19") (name "5V") (class "Default")
      (node (ref "5V") (pin "1") (pinfunction "3_1") (pintype "passive"))
      (node (ref "5V1") (pin "1") (pinfunction "3_1") (pintype "passive"))
      (node (ref "C3") (pin "+") (pinfunction "+_+") (pintype "passive"))
      (node (ref "IC2") (pin "3") (pinfunction "VO_3") (pintype "passive"))
      (node (ref "TEENSY_LC") (pin "VIN") (pinfunction "VIN_VIN") (pintype "power_in"))
    )
    (net (code "20") (name "GND") (class "Default")
      (node (ref "C1") (pin "-") (pinfunction "-_-") (pintype "passive"))
      (node (ref "C2") (pin "+") (pinfunction "+_+") (pintype "passive"))
      (node (ref "C29") (pin "+") (pinfunction "+_+") (pintype "passive"))
      (node (ref "C3") (pin "-") (pinfunction "-_-") (pintype "passive"))
      (node (ref "C4") (pin "1") (pinfunction "1_1") (pintype "passive"))
      (node (ref "C5") (pin "2") (pinfunction "2_2") (pintype "passive"))
      (node (ref "C6") (pin "1") (pinfunction "1_1") (pintype "passive"))
      (node (ref "C7") (pin "1") (pinfunction "1_1") (pintype "passive"))
      (node (ref "C8") (pin "2") (pinfunction "2_2") (pintype "passive"))
      (node (ref "GND") (pin "1") (pinfunction "3_1") (pintype "passive"))
      (node (ref "GND1") (pin "1") (pinfunction "3_1") (pintype "passive"))
      (node (ref "GND2") (pin "1") (pinfunction "3_1") (pintype "passive"))
      (node (ref "GND3") (pin "1") (pinfunction "3_1") (pintype "passive"))
      (node (ref "GND4") (pin "1") (pinfunction "3_1") (pintype "passive"))
      (node (ref "IC1") (pin "10") (pinfunction "+IN_10") (pintype "input"))
      (node (ref "IC1") (pin "12") (pinfunction "+IN_12") (pintype "input"))
      (node (ref "IC1") (pin "3") (pinfunction "+IN_3") (pintype "input"))
      (node (ref "IC1") (pin "5") (pinfunction "+IN_5") (pintype "input"))
      (node (ref "IC2") (pin "2") (pinfunction "GND_2") (pintype "passive"))
      (node (ref "IC3") (pin "5") (pinfunction "GND_5") (pintype "power_in"))
      (node (ref "IC4") (pin "5") (pinfunction "GND_5") (pintype "power_in"))
      (node (ref "IC5") (pin "10") (pinfunction "+IN_10") (pintype "input"))
      (node (ref "IC5") (pin "12") (pinfunction "+IN_12") (pintype "input"))
      (node (ref "IC5") (pin "3") (pinfunction "+IN_3") (pintype "input"))
      (node (ref "IC5") (pin "5") (pinfunction "+IN_5") (pintype "input"))
      (node (ref "IC6") (pin "10") (pinfunction "+IN_10") (pintype "input"))
      (node (ref "IC6") (pin "12") (pinfunction "+IN_12") (pintype "input"))
      (node (ref "IC6") (pin "3") (pinfunction "+IN_3") (pintype "input"))
      (node (ref "IC6") (pin "5") (pinfunction "+IN_5") (pintype "input"))
      (node (ref "IC7") (pin "1") (pinfunction "GND_1") (pintype "passive"))
      (node (ref "IC8") (pin "2") (pinfunction "C_2") (pintype "input"))
      (node (ref "Q1") (pin "3") (pinfunction "E_3") (pintype "passive"))
      (node (ref "Q2") (pin "3") (pinfunction "E_3") (pintype "passive"))
      (node (ref "Q3") (pin "3") (pinfunction "E_3") (pintype "passive"))
      (node (ref "Q4") (pin "3") (pinfunction "E_3") (pintype "passive"))
      (node (ref "Q5") (pin "3") (pinfunction "E_3") (pintype "passive"))
      (node (ref "Q6") (pin "3") (pinfunction "E_3") (pintype "passive"))
      (node (ref "R24") (pin "1") (pinfunction "1_1") (pintype "passive"))
      (node (ref "R37") (pin "1") (pinfunction "1_1") (pintype "passive"))
      (node (ref "R53") (pin "1") (pinfunction "1_1") (pintype "passive"))
      (node (ref "R56") (pin "1") (pinfunction "1_1") (pintype "passive"))
      (node (ref "R60") (pin "1") (pinfunction "1_1") (pintype "passive"))
      (node (ref "R65") (pin "1") (pinfunction "1_1") (pintype "passive"))
      (node (ref "TEENSY_LC") (pin "AGND") (pinfunction "GND_AGND") (pintype "power_in"))
      (node (ref "TEENSY_LC") (pin "GND") (pinfunction "GND_GND") (pintype "power_in"))
    )
    (net (code "21") (name "Net-(0_RX-3)") (class "Default")
      (node (ref "0_RX") (pin "1") (pinfunction "3_1") (pintype "passive"))
      (node (ref "TEENSY_LC") (pin "0") (pinfunction "0/RX1/T/MOSI1_0") (pintype "bidirectional"))
    )
    (net (code "22") (name "Net-(1_TX-3)") (class "Default")
      (node (ref "1_TX") (pin "1") (pinfunction "3_1") (pintype "passive"))
      (node (ref "TEENSY_LC") (pin "1") (pinfunction "1/TX1/T/MISO1_1") (pintype "bidirectional"))
    )
    (net (code "23") (name "Net-(10_CS-3)") (class "Default")
      (node (ref "10_CS") (pin "1") (pinfunction "3_1") (pintype "passive"))
      (node (ref "TEENSY_LC") (pin "10") (pinfunction "10/TX2/PWM_10") (pintype "bidirectional"))
    )
    (net (code "24") (name "Net-(11_MOSI-3)") (class "Default")
      (node (ref "11_MOSI") (pin "1") (pinfunction "3_1") (pintype "passive"))
      (node (ref "TEENSY_LC") (pin "11") (pinfunction "11/MOSI_11") (pintype "bidirectional"))
    )
    (net (code "25") (name "Net-(12_MISO-3)") (class "Default")
      (node (ref "12_MISO") (pin "1") (pinfunction "3_1") (pintype "passive"))
      (node (ref "TEENSY_LC") (pin "12") (pinfunction "12/MISO_12") (pintype "bidirectional"))
    )
    (net (code "26") (name "Net-(13_SCK-3)") (class "Default")
      (node (ref "13_SCK") (pin "1") (pinfunction "3_1") (pintype "passive"))
      (node (ref "TEENSY_LC") (pin "13") (pinfunction "13/SCK/LED_13") (pintype "bidirectional"))
    )
    (net (code "27") (name "Net-(CLKIN-3)") (class "Default")
      (node (ref "CLKIN") (pin "1") (pinfunction "3_1") (pintype "passive"))
      (node (ref "R55") (pin "1") (pinfunction "1_1") (pintype "passive"))
    )
    (net (code "28") (name "Net-(CV1A-3)") (class "Default")
      (node (ref "CV1A") (pin "1") (pinfunction "3_1") (pintype "passive"))
      (node (ref "R22") (pin "1") (pinfunction "1_1") (pintype "passive"))
    )
    (net (code "29") (name "Net-(CV1B-3)") (class "Default")
      (node (ref "CV1B") (pin "1") (pinfunction "3_1") (pintype "passive"))
      (node (ref "R23") (pin "1") (pinfunction "1_1") (pintype "passive"))
    )
    (net (code "30") (name "Net-(CV2A-3)") (class "Default")
      (node (ref "CV2A") (pin "1") (pinfunction "3_1") (pintype "passive"))
      (node (ref "R27") (pin "1") (pinfunction "1_1") (pintype "passive"))
    )
    (net (code "31") (name "Net-(CV2B-3)") (class "Default")
      (node (ref "CV2B") (pin "1") (pinfunction "3_1") (pintype "passive"))
      (node (ref "R28") (pin "1") (pinfunction "1_1") (pintype "passive"))
    )
    (net (code "32") (name "Net-(CV3A-3)") (class "Default")
      (node (ref "CV3A") (pin "1") (pinfunction "3_1") (pintype "passive"))
      (node (ref "R31") (pin "1") (pinfunction "1_1") (pintype "passive"))
    )
    (net (code "33") (name "Net-(CV3B-3)") (class "Default")
      (node (ref "CV3B") (pin "1") (pinfunction "3_1") (pintype "passive"))
      (node (ref "R32") (pin "1") (pinfunction "1_1") (pintype "passive"))
    )
    (net (code "34") (name "Net-(CV4A-3)") (class "Default")
      (node (ref "CV4A") (pin "1") (pinfunction "3_1") (pintype "passive"))
      (node (ref "R35") (pin "1") (pinfunction "1_1") (pintype "passive"))
    )
    (net (code "35") (name "Net-(CV4B-3)") (class "Default")
      (node (ref "CV4B") (pin "1") (pinfunction "3_1") (pintype "passive"))
      (node (ref "R36") (pin "1") (pinfunction "1_1") (pintype "passive"))
    )
    (net (code "36") (name "Net-(CV5A-3)") (class "Default")
      (node (ref "CV5A") (pin "1") (pinfunction "3_1") (pintype "passive"))
      (node (ref "R39") (pin "1") (pinfunction "1_1") (pintype "passive"))
    )
    (net (code "37") (name "Net-(CV5B-3)") (class "Default")
      (node (ref "CV5B") (pin "1") (pinfunction "3_1") (pintype "passive"))
      (node (ref "R40") (pin "1") (pinfunction "1_1") (pintype "passive"))
    )
    (net (code "38") (name "Net-(CV6A-3)") (class "Default")
      (node (ref "CV6A") (pin "1") (pinfunction "3_1") (pintype "passive"))
      (node (ref "R44") (pin "1") (pinfunction "1_1") (pintype "passive"))
    )
    (net (code "39") (name "Net-(CV6B-3)") (class "Default")
      (node (ref "CV6B") (pin "1") (pinfunction "3_1") (pintype "passive"))
      (node (ref "R45") (pin "1") (pinfunction "1_1") (pintype "passive"))
    )
    (net (code "40") (name "Net-(CV7A-3)") (class "Default")
      (node (ref "CV7A") (pin "1") (pinfunction "3_1") (pintype "passive"))
      (node (ref "R47") (pin "1") (pinfunction "1_1") (pintype "passive"))
    )
    (net (code "41") (name "Net-(CV7B-3)") (class "Default")
      (node (ref "CV7B") (pin "1") (pinfunction "3_1") (pintype "passive"))
      (node (ref "R48") (pin "1") (pinfunction "1_1") (pintype "passive"))
    )
    (net (code "42") (name "Net-(CV8A-3)") (class "Default")
      (node (ref "CV8A") (pin "1") (pinfunction "3_1") (pintype "passive"))
      (node (ref "R51") (pin "1") (pinfunction "1_1") (pintype "passive"))
    )
    (net (code "43") (name "Net-(CV8B-3)") (class "Default")
      (node (ref "CV8B") (pin "1") (pinfunction "3_1") (pintype "passive"))
      (node (ref "R52") (pin "1") (pinfunction "1_1") (pintype "passive"))
    )
    (net (code "44") (name "Net-(IC1A--IN)") (class "Default")
      (node (ref "C16") (pin "1") (pinfunction "1_1") (pintype "passive"))
      (node (ref "IC1") (pin "2") (pinfunction "-IN_2") (pintype "input"))
      (node (ref "R21") (pin "1") (pinfunction "1_1") (pintype "passive"))
      (node (ref "R22") (pin "2") (pinfunction "2_2") (pintype "passive"))
      (node (ref "R23") (pin "2") (pinfunction "2_2") (pintype "passive"))
    )
    (net (code "45") (name "Net-(IC1A-OUT)") (class "Default")
      (node (ref "C16") (pin "2") (pinfunction "2_2") (pintype "passive"))
      (node (ref "IC1") (pin "1") (pinfunction "OUT_1") (pintype "output"))
      (node (ref "IC3") (pin "3") (pinfunction "S_3") (pintype "bidirectional"))
      (node (ref "R21") (pin "2") (pinfunction "2_2") (pintype "passive"))
    )
    (net (code "46") (name "Net-(IC1B--IN)") (class "Default")
      (node (ref "C17") (pin "1") (pinfunction "1_1") (pintype "passive"))
      (node (ref "IC1") (pin "6") (pinfunction "-IN_6") (pintype "input"))
      (node (ref "R25") (pin "1") (pinfunction "1_1") (pintype "passive"))
      (node (ref "R27") (pin "2") (pinfunction "2_2") (pintype "passive"))
      (node (ref "R28") (pin "2") (pinfunction "2_2") (pintype "passive"))
    )
    (net (code "47") (name "Net-(IC1B-OUT)") (class "Default")
      (node (ref "C17") (pin "2") (pinfunction "2_2") (pintype "passive"))
      (node (ref "IC1") (pin "7") (pinfunction "OUT_7") (pintype "output"))
      (node (ref "IC3") (pin "14") (pinfunction "S_14") (pintype "bidirectional"))
      (node (ref "R25") (pin "2") (pinfunction "2_2") (pintype "passive"))
    )
    (net (code "48") (name "Net-(IC1C--IN)") (class "Default")
      (node (ref "C20") (pin "1") (pinfunction "1_1") (pintype "passive"))
      (node (ref "IC1") (pin "9") (pinfunction "-IN_9") (pintype "input"))
      (node (ref "R30") (pin "1") (pinfunction "1_1") (pintype "passive"))
      (node (ref "R31") (pin "2") (pinfunction "2_2") (pintype "passive"))
      (node (ref "R32") (pin "2") (pinfunction "2_2") (pintype "passive"))
    )
    (net (code "49") (name "Net-(IC1C-OUT)") (class "Default")
      (node (ref "C20") (pin "2") (pinfunction "2_2") (pintype "passive"))
      (node (ref "IC1") (pin "8") (pinfunction "OUT_8") (pintype "output"))
      (node (ref "IC3") (pin "11") (pinfunction "S_11") (pintype "bidirectional"))
      (node (ref "R30") (pin "2") (pinfunction "2_2") (pintype "passive"))
    )
    (net (code "50") (name "Net-(IC1D--IN)") (class "Default")
      (node (ref "C21") (pin "1") (pinfunction "1_1") (pintype "passive"))
      (node (ref "IC1") (pin "13") (pinfunction "-IN_13") (pintype "input"))
      (node (ref "R34") (pin "1") (pinfunction "1_1") (pintype "passive"))
      (node (ref "R35") (pin "2") (pinfunction "2_2") (pintype "passive"))
      (node (ref "R36") (pin "2") (pinfunction "2_2") (pintype "passive"))
    )
    (net (code "51") (name "Net-(IC1D-OUT)") (class "Default")
      (node (ref "C21") (pin "2") (pinfunction "2_2") (pintype "passive"))
      (node (ref "IC1") (pin "14") (pinfunction "OUT_14") (pintype "output"))
      (node (ref "IC3") (pin "6") (pinfunction "S_6") (pintype "bidirectional"))
      (node (ref "R34") (pin "2") (pinfunction "2_2") (pintype "passive"))
    )
    (net (code "52") (name "Net-(IC3A-D)") (class "Default")
      (node (ref "IC3") (pin "2") (pinfunction "D_2") (pintype "bidirectional"))
      (node (ref "R5") (pin "1") (pinfunction "1_1") (pintype "passive"))
    )
    (net (code "53") (name "Net-(IC3B-D)") (class "Default")
      (node (ref "IC3") (pin "15") (pinfunction "D_15") (pintype "bidirectional"))
      (node (ref "R2") (pin "1") (pinfunction "1_1") (pintype "passive"))
    )
    (net (code "54") (name "Net-(IC3C-D)") (class "Default")
      (node (ref "IC3") (pin "10") (pinfunction "D_10") (pintype "bidirectional"))
      (node (ref "R3") (pin "1") (pinfunction "1_1") (pintype "passive"))
    )
    (net (code "55") (name "Net-(IC3D-D)") (class "Default")
      (node (ref "IC3") (pin "7") (pinfunction "D_7") (pintype "bidirectional"))
      (node (ref "R4") (pin "1") (pinfunction "1_1") (pintype "passive"))
    )
    (net (code "56") (name "Net-(IC4A-D)") (class "Default")
      (node (ref "IC4") (pin "2") (pinfunction "D_2") (pintype "bidirectional"))
      (node (ref "R12") (pin "1") (pinfunction "1_1") (pintype "passive"))
    )
    (net (code "57") (name "Net-(IC4A-S)") (class "Default")
      (node (ref "C22") (pin "2") (pinfunction "2_2") (pintype "passive"))
      (node (ref "IC4") (pin "3") (pinfunction "S_3") (pintype "bidirectional"))
      (node (ref "IC6") (pin "1") (pinfunction "OUT_1") (pintype "output"))
      (node (ref "R38") (pin "2") (pinfunction "2_2") (pintype "passive"))
    )
    (net (code "58") (name "Net-(IC4B-D)") (class "Default")
      (node (ref "IC4") (pin "15") (pinfunction "D_15") (pintype "bidirectional"))
      (node (ref "R9") (pin "1") (pinfunction "1_1") (pintype "passive"))
    )
    (net (code "59") (name "Net-(IC4B-S)") (class "Default")
      (node (ref "C23") (pin "2") (pinfunction "2_2") (pintype "passive"))
      (node (ref "IC4") (pin "14") (pinfunction "S_14") (pintype "bidirectional"))
      (node (ref "IC6") (pin "7") (pinfunction "OUT_7") (pintype "output"))
      (node (ref "R42") (pin "2") (pinfunction "2_2") (pintype "passive"))
    )
    (net (code "60") (name "Net-(IC4C-D)") (class "Default")
      (node (ref "IC4") (pin "10") (pinfunction "D_10") (pintype "bidirectional"))
      (node (ref "R10") (pin "1") (pinfunction "1_1") (pintype "passive"))
    )
    (net (code "61") (name "Net-(IC4C-S)") (class "Default")
      (node (ref "C24") (pin "2") (pinfunction "2_2") (pintype "passive"))
      (node (ref "IC4") (pin "11") (pinfunction "S_11") (pintype "bidirectional"))
      (node (ref "IC6") (pin "8") (pinfunction "OUT_8") (pintype "output"))
      (node (ref "R46") (pin "2") (pinfunction "2_2") (pintype "passive"))
    )
    (net (code "62") (name "Net-(IC4D-D)") (class "Default")
      (node (ref "IC4") (pin "7") (pinfunction "D_7") (pintype "bidirectional"))
      (node (ref "R11") (pin "1") (pinfunction "1_1") (pintype "passive"))
    )
    (net (code "63") (name "Net-(IC4D-S)") (class "Default")
      (node (ref "C25") (pin "2") (pinfunction "2_2") (pintype "passive"))
      (node (ref "IC4") (pin "6") (pinfunction "S_6") (pintype "bidirectional"))
      (node (ref "IC6") (pin "14") (pinfunction "OUT_14") (pintype "output"))
      (node (ref "R50") (pin "2") (pinfunction "2_2") (pintype "passive"))
    )
    (net (code "64") (name "Net-(IC5A--IN)") (class "Default")
      (node (ref "C9") (pin "1") (pinfunction "1_1") (pintype "passive"))
      (node (ref "IC5") (pin "2") (pinfunction "-IN_2") (pintype "input"))
      (node (ref "R1") (pin "1") (pinfunction "1_1") (pintype "passive"))
      (node (ref "R2") (pin "2") (pinfunction "2_2") (pintype "passive"))
      (node (ref "R3") (pin "2") (pinfunction "2_2") (pintype "passive"))
      (node (ref "R4") (pin "2") (pinfunction "2_2") (pintype "passive"))
      (node (ref "R5") (pin "2") (pinfunction "2_2") (pintype "passive"))
    )
    (net (code "65") (name "Net-(IC5A-OUT)") (class "Default")
      (node (ref "C9") (pin "2") (pinfunction "2_2") (pintype "passive"))
      (node (ref "IC5") (pin "1") (pinfunction "OUT_1") (pintype "output"))
      (node (ref "R1") (pin "2") (pinfunction "2_2") (pintype "passive"))
      (node (ref "R17") (pin "1") (pinfunction "1_1") (pintype "passive"))
      (node (ref "R6") (pin "1") (pinfunction "1_1") (pintype "passive"))
    )
    (net (code "66") (name "Net-(IC5B--IN)") (class "Default")
      (node (ref "C10") (pin "1") (pinfunction "1_1") (pintype "passive"))
      (node (ref "IC5") (pin "6") (pinfunction "-IN_6") (pintype "input"))
      (node (ref "R10") (pin "2") (pinfunction "2_2") (pintype "passive"))
      (node (ref "R11") (pin "2") (pinfunction "2_2") (pintype "passive"))
      (node (ref "R12") (pin "2") (pinfunction "2_2") (pintype "passive"))
      (node (ref "R8") (pin "1") (pinfunction "1_1") (pintype "passive"))
      (node (ref "R9") (pin "2") (pinfunction "2_2") (pintype "passive"))
    )
    (net (code "67") (name "Net-(IC5B-OUT)") (class "Default")
      (node (ref "C10") (pin "2") (pinfunction "2_2") (pintype "passive"))
      (node (ref "IC5") (pin "7") (pinfunction "OUT_7") (pintype "output"))
      (node (ref "R13") (pin "1") (pinfunction "1_1") (pintype "passive"))
      (node (ref "R18") (pin "1") (pinfunction "1_1") (pintype "passive"))
      (node (ref "R8") (pin "2") (pinfunction "2_2") (pintype "passive"))
    )
    (net (code "68") (name "Net-(IC5C--IN)") (class "Default")
      (node (ref "C11") (pin "1") (pinfunction "1_1") (pintype "passive"))
      (node (ref "IC5") (pin "9") (pinfunction "-IN_9") (pintype "input"))
      (node (ref "R14") (pin "1") (pinfunction "1_1") (pintype "passive"))
      (node (ref "R17") (pin "2") (pinfunction "2_2") (pintype "passive"))
      (node (ref "R18") (pin "2") (pinfunction "2_2") (pintype "passive"))
    )
    (net (code "69") (name "Net-(IC5C-OUT)") (class "Default")
      (node (ref "C11") (pin "2") (pinfunction "2_2") (pintype "passive"))
      (node (ref "IC5") (pin "8") (pinfunction "OUT_8") (pintype "output"))
      (node (ref "R14") (pin "2") (pinfunction "2_2") (pintype "passive"))
      (node (ref "R16") (pin "1") (pinfunction "1_1") (pintype "passive"))
    )
    (net (code "70") (name "Net-(IC5D--IN)") (class "Default")
      (node (ref "C12") (pin "1") (pinfunction "1_1") (pintype "passive"))
      (node (ref "IC5") (pin "13") (pinfunction "-IN_13") (pintype "input"))
      (node (ref "R15") (pin "1") (pinfunction "1_1") (pintype "passive"))
      (node (ref "R16") (pin "2") (pinfunction "2_2") (pintype "passive"))
    )
    (net (code "71") (name "Net-(IC5D-OUT)") (class "Default")
      (node (ref "C12") (pin "2") (pinfunction "2_2") (pintype "passive"))
      (node (ref "IC5") (pin "14") (pinfunction "OUT_14") (pintype "output"))
      (node (ref "R15") (pin "2") (pinfunction "2_2") (pintype "passive"))
      (node (ref "R67") (pin "1") (pinfunction "1_1") (pintype "passive"))
    )
    (net (code "72") (name "Net-(IC6A--IN)") (class "Default")
      (node (ref "C22") (pin "1") (pinfunction "1_1") (pintype "passive"))
      (node (ref "IC6") (pin "2") (pinfunction "-IN_2") (pintype "input"))
      (node (ref "R38") (pin "1") (pinfunction "1_1") (pintype "passive"))
      (node (ref "R39") (pin "2") (pinfunction "2_2") (pintype "passive"))
      (node (ref "R40") (pin "2") (pinfunction "2_2") (pintype "passive"))
    )
    (net (code "73") (name "Net-(IC6B--IN)") (class "Default")
      (node (ref "C23") (pin "1") (pinfunction "1_1") (pintype "passive"))
      (node (ref "IC6") (pin "6") (pinfunction "-IN_6") (pintype "input"))
      (node (ref "R42") (pin "1") (pinfunction "1_1") (pintype "passive"))
      (node (ref "R44") (pin "2") (pinfunction "2_2") (pintype "passive"))
      (node (ref "R45") (pin "2") (pinfunction "2_2") (pintype "passive"))
    )
    (net (code "74") (name "Net-(IC6C--IN)") (class "Default")
      (node (ref "C24") (pin "1") (pinfunction "1_1") (pintype "passive"))
      (node (ref "IC6") (pin "9") (pinfunction "-IN_9") (pintype "input"))
      (node (ref "R46") (pin "1") (pinfunction "1_1") (pintype "passive"))
      (node (ref "R47") (pin "2") (pinfunction "2_2") (pintype "passive"))
      (node (ref "R48") (pin "2") (pinfunction "2_2") (pintype "passive"))
    )
    (net (code "75") (name "Net-(IC6D--IN)") (class "Default")
      (node (ref "C25") (pin "1") (pinfunction "1_1") (pintype "passive"))
      (node (ref "IC6") (pin "13") (pinfunction "-IN_13") (pintype "input"))
      (node (ref "R50") (pin "1") (pinfunction "1_1") (pintype "passive"))
      (node (ref "R51") (pin "2") (pinfunction "2_2") (pintype "passive"))
      (node (ref "R52") (pin "2") (pinfunction "2_2") (pintype "passive"))
    )
    (net (code "76") (name "Net-(OUT1-3)") (class "Default")
      (node (ref "OUT1") (pin "1") (pinfunction "3_1") (pintype "passive"))
      (node (ref "R6") (pin "2") (pinfunction "2_2") (pintype "passive"))
    )
    (net (code "77") (name "Net-(OUT2-3)") (class "Default")
      (node (ref "OUT2") (pin "1") (pinfunction "3_1") (pintype "passive"))
      (node (ref "R13") (pin "2") (pinfunction "2_2") (pintype "passive"))
    )
    (net (code "78") (name "Net-(OUTSUM-3)") (class "Default")
      (node (ref "OUTSUM") (pin "1") (pinfunction "3_1") (pintype "passive"))
      (node (ref "R67") (pin "2") (pinfunction "2_2") (pintype "passive"))
    )
    (net (code "79") (name "Net-(Q1-B)") (class "Default")
      (node (ref "Q1") (pin "2") (pinfunction "B_2") (pintype "passive"))
      (node (ref "R55") (pin "2") (pinfunction "2_2") (pintype "passive"))
      (node (ref "R56") (pin "2") (pinfunction "2_2") (pintype "passive"))
    )
    (net (code "80") (name "Net-(Q1-C)") (class "Default")
      (node (ref "Q1") (pin "1") (pinfunction "C_1") (pintype "passive"))
      (node (ref "R54") (pin "1") (pinfunction "1_1") (pintype "passive"))
      (node (ref "R57") (pin "1") (pinfunction "1_1") (pintype "passive"))
    )
    (net (code "81") (name "Net-(Q2-B)") (class "Default")
      (node (ref "Q2") (pin "2") (pinfunction "B_2") (pintype "passive"))
      (node (ref "R59") (pin "2") (pinfunction "2_2") (pintype "passive"))
      (node (ref "R60") (pin "2") (pinfunction "2_2") (pintype "passive"))
    )
    (net (code "82") (name "Net-(Q2-C)") (class "Default")
      (node (ref "Q2") (pin "1") (pinfunction "C_1") (pintype "passive"))
      (node (ref "R58") (pin "1") (pinfunction "1_1") (pintype "passive"))
      (node (ref "R61") (pin "1") (pinfunction "1_1") (pintype "passive"))
    )
    (net (code "83") (name "Net-(Q3-B)") (class "Default")
      (node (ref "Q3") (pin "2") (pinfunction "B_2") (pintype "passive"))
      (node (ref "R20") (pin "2") (pinfunction "2_2") (pintype "passive"))
      (node (ref "R24") (pin "2") (pinfunction "2_2") (pintype "passive"))
    )
    (net (code "84") (name "Net-(Q3-C)") (class "Default")
      (node (ref "Q3") (pin "1") (pinfunction "C_1") (pintype "passive"))
      (node (ref "R19") (pin "1") (pinfunction "1_1") (pintype "passive"))
      (node (ref "R26") (pin "1") (pinfunction "1_1") (pintype "passive"))
    )
    (net (code "85") (name "Net-(Q4-B)") (class "Default")
      (node (ref "Q4") (pin "2") (pinfunction "B_2") (pintype "passive"))
      (node (ref "R33") (pin "2") (pinfunction "2_2") (pintype "passive"))
      (node (ref "R37") (pin "2") (pinfunction "2_2") (pintype "passive"))
    )
    (net (code "86") (name "Net-(Q4-C)") (class "Default")
      (node (ref "Q4") (pin "1") (pinfunction "C_1") (pintype "passive"))
      (node (ref "R29") (pin "1") (pinfunction "1_1") (pintype "passive"))
      (node (ref "R41") (pin "1") (pinfunction "1_1") (pintype "passive"))
    )
    (net (code "87") (name "Net-(Q5-B)") (class "Default")
      (node (ref "Q5") (pin "2") (pinfunction "B_2") (pintype "passive"))
      (node (ref "R49") (pin "2") (pinfunction "2_2") (pintype "passive"))
      (node (ref "R53") (pin "2") (pinfunction "2_2") (pintype "passive"))
    )
    (net (code "88") (name "Net-(Q5-C)") (class "Default")
      (node (ref "Q5") (pin "1") (pinfunction "C_1") (pintype "passive"))
      (node (ref "R43") (pin "1") (pinfunction "1_1") (pintype "passive"))
      (node (ref "R62") (pin "1") (pinfunction "1_1") (pintype "passive"))
    )
    (net (code "89") (name "Net-(Q6-B)") (class "Default")
      (node (ref "Q6") (pin "2") (pinfunction "B_2") (pintype "passive"))
      (node (ref "R64") (pin "2") (pinfunction "2_2") (pintype "passive"))
      (node (ref "R65") (pin "2") (pinfunction "2_2") (pintype "passive"))
    )
    (net (code "90") (name "Net-(Q6-C)") (class "Default")
      (node (ref "Q6") (pin "1") (pinfunction "C_1") (pintype "passive"))
      (node (ref "R63") (pin "1") (pinfunction "1_1") (pintype "passive"))
      (node (ref "R66") (pin "1") (pinfunction "1_1") (pintype "passive"))
    )
    (net (code "91") (name "Net-(RSTIN-3)") (class "Default")
      (node (ref "R59") (pin "1") (pinfunction "1_1") (pintype "passive"))
      (node (ref "RSTIN") (pin "1") (pinfunction "3_1") (pintype "passive"))
    )
    (net (code "92") (name "Net-(TRIG1-3)") (class "Default")
      (node (ref "R20") (pin "1") (pinfunction "1_1") (pintype "passive"))
      (node (ref "TRIG1") (pin "1") (pinfunction "3_1") (pintype "passive"))
    )
    (net (code "93") (name "Net-(TRIG2-3)") (class "Default")
      (node (ref "R33") (pin "1") (pinfunction "1_1") (pintype "passive"))
      (node (ref "TRIG2") (pin "1") (pinfunction "3_1") (pintype "passive"))
    )
    (net (code "94") (name "Net-(TRIG3-3)") (class "Default")
      (node (ref "R49") (pin "1") (pinfunction "1_1") (pintype "passive"))
      (node (ref "TRIG3") (pin "1") (pinfunction "3_1") (pintype "passive"))
    )
    (net (code "95") (name "Net-(TRIG4-3)") (class "Default")
      (node (ref "R64") (pin "1") (pinfunction "1_1") (pintype "passive"))
      (node (ref "TRIG4") (pin "1") (pinfunction "3_1") (pintype "passive"))
    )
    (net (code "96") (name "unconnected-(TEENSY_LC-20{slash}A6{slash}PWM{slash}SCK1-Pad20{slash}A6)") (class "Default")
      (node (ref "TEENSY_LC") (pin "20/A6") (pinfunction "20/A6/PWM/SCK1_20/A6") (pintype "bidirectional"))
    )
    (net (code "97") (name "unconnected-(TEENSY_LC-22{slash}A8{slash}T{slash}PWM{slash}SCL1-Pad22{slash}A8)") (class "Default")
      (node (ref "TEENSY_LC") (pin "22/A8") (pinfunction "22/A8/T/PWM/SCL1_22/A8") (pintype "bidirectional"))
    )
    (net (code "98") (name "unconnected-(TEENSY_LC-23{slash}A9{slash}T{slash}PWM{slash}SDA1-Pad23{slash}A9)") (class "Default")
      (node (ref "TEENSY_LC") (pin "23/A9") (pinfunction "23/A9/T/PWM/SDA1_23/A9") (pintype "bidirectional"))
    )
    (net (code "99") (name "unconnected-(TEENSY_LC-Pad21{slash}A7)") (class "Default")
      (node (ref "TEENSY_LC") (pin "21/A7") (pinfunction "21/A7_21/A7") (pintype "bidirectional"))
    )
  )
)
